# decoder.net
KiCad netlist of a schematic drawn in EAGLE
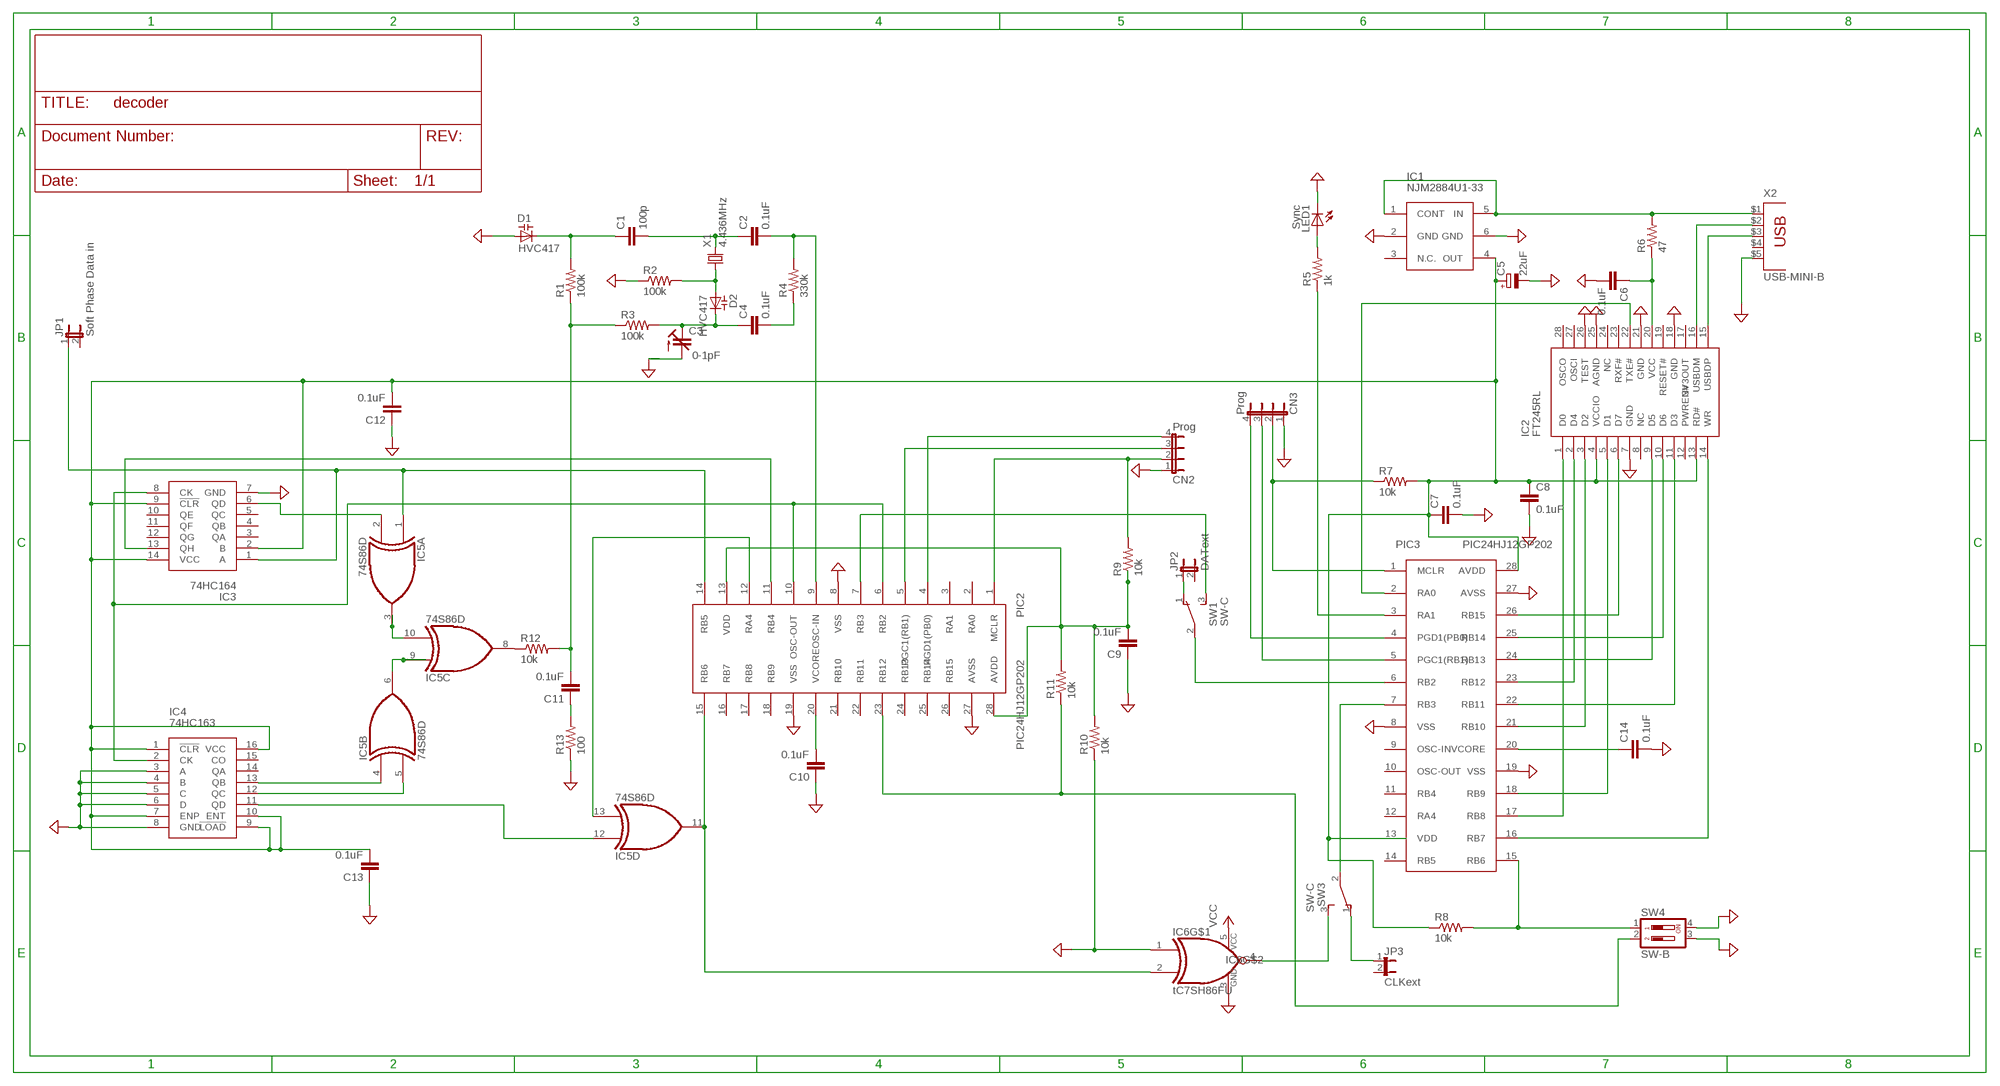
[diagram p0: schematic, sheet 1]

(export (version "E")
  (design (tool "Eeschema 10.0.6"))
  (components
    (comp (ref "C1")
      (value "100p")
      (footprint "eagle-import:C025-025X050")
      (libsource (lib "eagle-import") (part "C-EU025-025X050"))
    )
    (comp (ref "C2")
      (value "0.1uF")
      (footprint "eagle-import:C050-025X075")
      (libsource (lib "eagle-import") (part "resistor_C-EU050-025X075"))
    )
    (comp (ref "C3")
      (value "0-1pF")
      (footprint "eagle-import:CTRIMTZ03")
      (libsource (lib "eagle-import") (part "C-TRIMMTZ03"))
    )
    (comp (ref "C4")
      (value "0.1uF")
      (footprint "eagle-import:C050-025X075")
      (libsource (lib "eagle-import") (part "resistor_C-EU050-025X075"))
    )
    (comp (ref "C5")
      (value "22uF")
      (footprint "eagle-import:E3,5-8")
      (libsource (lib "eagle-import") (part "CPOL-EUE3.5-8"))
    )
    (comp (ref "C6")
      (value "0.1uF")
      (footprint "eagle-import:C050-025X075")
      (libsource (lib "eagle-import") (part "resistor_C-EU050-025X075"))
    )
    (comp (ref "C7")
      (value "0.1uF")
      (footprint "eagle-import:C050-025X075")
      (libsource (lib "eagle-import") (part "resistor_C-EU050-025X075"))
    )
    (comp (ref "C8")
      (value "0.1uF")
      (footprint "eagle-import:C050-025X075")
      (libsource (lib "eagle-import") (part "resistor_C-EU050-025X075"))
    )
    (comp (ref "C9")
      (value "0.1uF")
      (footprint "eagle-import:C050-025X075")
      (libsource (lib "eagle-import") (part "resistor_C-EU050-025X075"))
    )
    (comp (ref "C10")
      (value "0.1uF")
      (footprint "eagle-import:C050-025X075")
      (libsource (lib "eagle-import") (part "resistor_C-EU050-025X075"))
    )
    (comp (ref "C11")
      (value "0.1uF")
      (footprint "eagle-import:C050-025X075")
      (libsource (lib "eagle-import") (part "resistor_C-EU050-025X075"))
    )
    (comp (ref "C12")
      (value "0.1uF")
      (footprint "eagle-import:C050-025X075")
      (libsource (lib "eagle-import") (part "resistor_C-EU050-025X075"))
    )
    (comp (ref "C13")
      (value "0.1uF")
      (footprint "eagle-import:C050-025X075")
      (libsource (lib "eagle-import") (part "resistor_C-EU050-025X075"))
    )
    (comp (ref "C14")
      (value "0.1uF")
      (footprint "eagle-import:C050-025X075")
      (libsource (lib "eagle-import") (part "resistor_C-EU050-025X075"))
    )
    (comp (ref "CN2")
      (value "Prog")
      (footprint "eagle-import:JP4")
      (libsource (lib "eagle-import") (part "JP4E"))
    )
    (comp (ref "CN3")
      (value "Prog")
      (footprint "eagle-import:JP4")
      (libsource (lib "eagle-import") (part "JP4E"))
    )
    (comp (ref "D1")
      (value "HVC417")
      (footprint "eagle-import:SOT54H")
      (libsource (lib "eagle-import") (part "BB112"))
    )
    (comp (ref "D2")
      (value "HVC417")
      (footprint "eagle-import:SOT54H")
      (libsource (lib "eagle-import") (part "BB112"))
    )
    (comp (ref "IC1")
      (value "NJM2884U1-33")
      (footprint "eagle-import:NJM2884U1-33")
      (libsource (lib "eagle-import") (part "NJM2884U1-33"))
    )
    (comp (ref "IC2")
      (value "FT245RL")
      (footprint "eagle-import:FT245RL")
      (libsource (lib "eagle-import") (part "FT245RL"))
    )
    (comp (ref "IC3")
      (value "74HC164")
      (footprint "eagle-import:74HC164")
      (libsource (lib "eagle-import") (part "74HC164"))
    )
    (comp (ref "IC4")
      (value "74HC163")
      (footprint "eagle-import:74HC163")
      (libsource (lib "eagle-import") (part "74HC163"))
    )
    (comp (ref "IC5")
      (value "74S86D")
      (footprint "eagle-import:SO14")
      (libsource (lib "eagle-import") (part "7486DS"))
    )
    (comp (ref "IC6")
      (value "tC7SH86FU")
      (footprint "eagle-import:TC7SH86FU")
      (libsource (lib "eagle-import") (part "TC7SH86FU"))
    )
    (comp (ref "JP1")
      (value "Soft Phase Data in")
      (footprint "eagle-import:JP1")
      (libsource (lib "eagle-import") (part "JP1E"))
    )
    (comp (ref "JP2")
      (value "DAText")
      (footprint "eagle-import:JP1")
      (libsource (lib "eagle-import") (part "JP1E"))
    )
    (comp (ref "JP3")
      (value "CLKext")
      (footprint "eagle-import:JP1")
      (libsource (lib "eagle-import") (part "JP1E"))
    )
    (comp (ref "LED1")
      (value "Sync")
      (footprint "eagle-import:LED5MM")
      (libsource (lib "eagle-import") (part "LED5MM"))
    )
    (comp (ref "PIC2")
      (value "PIC24HJ12GP202")
      (footprint "eagle-import:PIC24HJ12GP202")
      (libsource (lib "eagle-import") (part "PIC24HJ12GP202"))
    )
    (comp (ref "PIC3")
      (value "PIC24HJ12GP202")
      (footprint "eagle-import:PIC24HJ12GP202")
      (libsource (lib "eagle-import") (part "PIC24HJ12GP202"))
    )
    (comp (ref "R1")
      (value "100k")
      (footprint "eagle-import:0207_7")
      (libsource (lib "eagle-import") (part "R-US_0207/7"))
    )
    (comp (ref "R2")
      (value "100k")
      (footprint "eagle-import:0207_7")
      (libsource (lib "eagle-import") (part "R-US_0207/7"))
    )
    (comp (ref "R3")
      (value "100k")
      (footprint "eagle-import:0207_7")
      (libsource (lib "eagle-import") (part "R-US_0207/7"))
    )
    (comp (ref "R4")
      (value "330k")
      (footprint "eagle-import:0207_7")
      (libsource (lib "eagle-import") (part "R-US_0207/7"))
    )
    (comp (ref "R5")
      (value "1k")
      (footprint "eagle-import:0207_7")
      (libsource (lib "eagle-import") (part "R-US_0207/7"))
    )
    (comp (ref "R6")
      (value "47")
      (footprint "eagle-import:0207_7")
      (libsource (lib "eagle-import") (part "R-US_0207/7"))
    )
    (comp (ref "R7")
      (value "10k")
      (footprint "eagle-import:0207_7")
      (libsource (lib "eagle-import") (part "R-US_0207/7"))
    )
    (comp (ref "R8")
      (value "10k")
      (footprint "eagle-import:0207_7")
      (libsource (lib "eagle-import") (part "R-US_0207/7"))
    )
    (comp (ref "R9")
      (value "10k")
      (footprint "eagle-import:0207_7")
      (libsource (lib "eagle-import") (part "R-US_0207/7"))
    )
    (comp (ref "R10")
      (value "10k")
      (footprint "eagle-import:0207_7")
      (libsource (lib "eagle-import") (part "R-US_0207/7"))
    )
    (comp (ref "R11")
      (value "10k")
      (footprint "eagle-import:0207_7")
      (libsource (lib "eagle-import") (part "R-US_0207/7"))
    )
    (comp (ref "R12")
      (value "10k")
      (footprint "eagle-import:0207_7")
      (libsource (lib "eagle-import") (part "R-US_0207/7"))
    )
    (comp (ref "R13")
      (value "100")
      (footprint "eagle-import:0207_7")
      (libsource (lib "eagle-import") (part "R-US_0207/7"))
    )
    (comp (ref "SW1")
      (value "SW-C")
      (footprint "eagle-import:TL3XPO")
      (libsource (lib "eagle-import") (part "TL36PO"))
    )
    (comp (ref "SW3")
      (value "SW-C")
      (footprint "eagle-import:TL3XPO")
      (libsource (lib "eagle-import") (part "TL36PO"))
    )
    (comp (ref "SW4")
      (value "SW-B")
      (footprint "eagle-import:DIP02YL")
      (libsource (lib "eagle-import") (part "DIP02YL"))
    )
    (comp (ref "X1")
      (value "4.436MHz")
      (footprint "eagle-import:HC49_S")
      (libsource (lib "eagle-import") (part "CRYSTALHC49S"))
    )
    (comp (ref "X2")
      (value "USB-MINI-B")
      (footprint "eagle-import:USB-MINI-B")
      (libsource (lib "eagle-import") (part "USB-MINI-B"))
    )
  )
  (nets
    (net (code "1") (name "/VDD") (class "Default")
      (node (ref "PIC3") (pin "13") (pinfunction "VDD_13") (pintype "power_in"))
    )
    (net (code "2") (name "GND") (class "Default")
      (node (ref "C10") (pin "1") (pinfunction "1_1") (pintype "passive"))
      (node (ref "C12") (pin "1") (pinfunction "1_1") (pintype "passive"))
      (node (ref "C13") (pin "1") (pinfunction "1_1") (pintype "passive"))
      (node (ref "C14") (pin "2") (pinfunction "2_2") (pintype "passive"))
      (node (ref "C3") (pin "2") (pinfunction "A_2") (pintype "passive"))
      (node (ref "C5") (pin "-") (pinfunction "-_-") (pintype "passive"))
      (node (ref "C6") (pin "2") (pinfunction "2_2") (pintype "passive"))
      (node (ref "C7") (pin "2") (pinfunction "2_2") (pintype "passive"))
      (node (ref "C8") (pin "2") (pinfunction "2_2") (pintype "passive"))
      (node (ref "C9") (pin "1") (pinfunction "1_1") (pintype "passive"))
      (node (ref "CN2") (pin "1") (pinfunction "1_1") (pintype "passive"))
      (node (ref "CN3") (pin "1") (pinfunction "1_1") (pintype "passive"))
      (node (ref "D1") (pin "A") (pinfunction "A_A") (pintype "passive"))
      (node (ref "IC1") (pin "2") (pinfunction "GND_2") (pintype "power_in"))
      (node (ref "IC1") (pin "6") (pinfunction "GND_6") (pintype "power_in"))
      (node (ref "IC2") (pin "18") (pinfunction "GND_18") (pintype "power_in"))
      (node (ref "IC2") (pin "21") (pinfunction "GND_21") (pintype "power_in"))
      (node (ref "IC2") (pin "25") (pinfunction "AGND_25") (pintype "power_in"))
      (node (ref "IC2") (pin "26") (pinfunction "TEST_26") (pintype "input"))
      (node (ref "IC2") (pin "7") (pinfunction "GND_7") (pintype "power_in"))
      (node (ref "IC3") (pin "7") (pinfunction "GND_7") (pintype "power_in"))
      (node (ref "IC4") (pin "3") (pinfunction "A_3") (pintype "input"))
      (node (ref "IC4") (pin "4") (pinfunction "B_4") (pintype "input"))
      (node (ref "IC4") (pin "5") (pinfunction "C_5") (pintype "input"))
      (node (ref "IC4") (pin "6") (pinfunction "D_6") (pintype "input"))
      (node (ref "IC4") (pin "8") (pinfunction "GND_8") (pintype "power_in"))
      (node (ref "IC6") (pin "1") (pinfunction "I0_1") (pintype "input"))
      (node (ref "IC6") (pin "3") (pinfunction "GND_3") (pintype "power_in"))
      (node (ref "LED1") (pin "K") (pinfunction "C_K") (pintype "passive"))
      (node (ref "PIC2") (pin "19") (pinfunction "VSS_19") (pintype "power_in"))
      (node (ref "PIC2") (pin "27") (pinfunction "AVSS_27") (pintype "power_in"))
      (node (ref "PIC2") (pin "8") (pinfunction "VSS_8") (pintype "power_in"))
      (node (ref "PIC3") (pin "19") (pinfunction "VSS_19") (pintype "power_in"))
      (node (ref "PIC3") (pin "27") (pinfunction "AVSS_27") (pintype "power_in"))
      (node (ref "PIC3") (pin "8") (pinfunction "VSS_8") (pintype "power_in"))
      (node (ref "R10") (pin "1") (pinfunction "1_1") (pintype "passive"))
      (node (ref "R13") (pin "1") (pinfunction "1_1") (pintype "passive"))
      (node (ref "R2") (pin "1") (pinfunction "1_1") (pintype "passive"))
      (node (ref "SW4") (pin "3") (pinfunction "3_3") (pintype "passive"))
      (node (ref "SW4") (pin "4") (pinfunction "4_4") (pintype "passive"))
      (node (ref "X2") (pin "$5") (pinfunction "5_$5") (pintype "bidirectional"))
    )
    (net (code "3") (name "Net-(C1-Pad1)") (class "Default")
      (node (ref "C1") (pin "1") (pinfunction "1_1") (pintype "passive"))
      (node (ref "D1") (pin "C") (pinfunction "C_C") (pintype "passive"))
      (node (ref "R1") (pin "2") (pinfunction "2_2") (pintype "passive"))
    )
    (net (code "4") (name "Net-(C1-Pad2)") (class "Default")
      (node (ref "C1") (pin "2") (pinfunction "2_2") (pintype "passive"))
      (node (ref "C2") (pin "1") (pinfunction "1_1") (pintype "passive"))
      (node (ref "X1") (pin "2") (pinfunction "2_2") (pintype "passive"))
    )
    (net (code "5") (name "Net-(C3-E)") (class "Default")
      (node (ref "C3") (pin "1") (pinfunction "E_1") (pintype "passive"))
      (node (ref "C4") (pin "1") (pinfunction "1_1") (pintype "passive"))
      (node (ref "D2") (pin "C") (pinfunction "C_C") (pintype "passive"))
      (node (ref "R3") (pin "2") (pinfunction "2_2") (pintype "passive"))
    )
    (net (code "6") (name "Net-(C4-Pad2)") (class "Default")
      (node (ref "C4") (pin "2") (pinfunction "2_2") (pintype "passive"))
      (node (ref "R4") (pin "1") (pinfunction "1_1") (pintype "passive"))
    )
    (net (code "7") (name "Net-(C11-Pad1)") (class "Default")
      (node (ref "C11") (pin "1") (pinfunction "1_1") (pintype "passive"))
      (node (ref "R13") (pin "2") (pinfunction "2_2") (pintype "passive"))
    )
    (net (code "8") (name "Net-(C11-Pad2)") (class "Default")
      (node (ref "C11") (pin "2") (pinfunction "2_2") (pintype "passive"))
      (node (ref "R1") (pin "1") (pinfunction "1_1") (pintype "passive"))
      (node (ref "R12") (pin "2") (pinfunction "2_2") (pintype "passive"))
      (node (ref "R3") (pin "1") (pinfunction "1_1") (pintype "passive"))
    )
    (net (code "9") (name "Net-(D2-PadA)") (class "Default")
      (node (ref "D2") (pin "A") (pinfunction "A_A") (pintype "passive"))
      (node (ref "R2") (pin "2") (pinfunction "2_2") (pintype "passive"))
      (node (ref "X1") (pin "1") (pinfunction "1_1") (pintype "passive"))
    )
    (net (code "10") (name "Net-(IC1-CONT)") (class "Default")
      (node (ref "IC1") (pin "1") (pinfunction "CONT_1") (pintype "bidirectional"))
      (node (ref "IC1") (pin "5") (pinfunction "IN_5") (pintype "input"))
      (node (ref "R6") (pin "2") (pinfunction "2_2") (pintype "passive"))
      (node (ref "X2") (pin "$1") (pinfunction "1_$1") (pintype "bidirectional"))
    )
    (net (code "11") (name "Net-(IC1-OUT)") (class "Default")
      (node (ref "C12") (pin "2") (pinfunction "2_2") (pintype "passive"))
      (node (ref "C13") (pin "2") (pinfunction "2_2") (pintype "passive"))
      (node (ref "C5") (pin "+") (pinfunction "+_+") (pintype "passive"))
      (node (ref "C7") (pin "1") (pinfunction "1_1") (pintype "passive"))
      (node (ref "C8") (pin "1") (pinfunction "1_1") (pintype "passive"))
      (node (ref "IC1") (pin "4") (pinfunction "OUT_4") (pintype "output"))
      (node (ref "IC2") (pin "13") (pinfunction "RD#_13") (pintype "input"))
      (node (ref "IC2") (pin "4") (pinfunction "VCCIO_4") (pintype "power_in"))
      (node (ref "IC3") (pin "14") (pinfunction "VCC_14") (pintype "power_in"))
      (node (ref "IC3") (pin "2") (pinfunction "B_2") (pintype "input"))
      (node (ref "IC3") (pin "9") (pinfunction "~{CLR}_9") (pintype "input"))
      (node (ref "IC4") (pin "1") (pinfunction "~{CLR}_1") (pintype "input"))
      (node (ref "IC4") (pin "10") (pinfunction "ENT_10") (pintype "input"))
      (node (ref "IC4") (pin "16") (pinfunction "VCC_16") (pintype "power_in"))
      (node (ref "IC4") (pin "7") (pinfunction "ENP_7") (pintype "input"))
      (node (ref "IC4") (pin "9") (pinfunction "~{LOAD}_9") (pintype "input"))
      (node (ref "PIC3") (pin "28") (pinfunction "AVDD_28") (pintype "power_in"))
      (node (ref "R7") (pin "2") (pinfunction "2_2") (pintype "passive"))
      (node (ref "R8") (pin "1") (pinfunction "1_1") (pintype "passive"))
    )
    (net (code "12") (name "Net-(IC2-D0)") (class "Default")
      (node (ref "IC2") (pin "1") (pinfunction "D0_1") (pintype "bidirectional"))
      (node (ref "PIC3") (pin "17") (pinfunction "RB8_17") (pintype "bidirectional"))
    )
    (net (code "13") (name "Net-(IC2-D1)") (class "Default")
      (node (ref "IC2") (pin "5") (pinfunction "D1_5") (pintype "bidirectional"))
      (node (ref "PIC3") (pin "18") (pinfunction "RB9_18") (pintype "bidirectional"))
    )
    (net (code "14") (name "Net-(IC2-D2)") (class "Default")
      (node (ref "IC2") (pin "3") (pinfunction "D2_3") (pintype "bidirectional"))
      (node (ref "PIC3") (pin "21") (pinfunction "RB10_21") (pintype "bidirectional"))
    )
    (net (code "15") (name "Net-(IC2-D3)") (class "Default")
      (node (ref "IC2") (pin "11") (pinfunction "D3_11") (pintype "bidirectional"))
      (node (ref "PIC3") (pin "22") (pinfunction "RB11_22") (pintype "bidirectional"))
    )
    (net (code "16") (name "Net-(IC2-D4)") (class "Default")
      (node (ref "IC2") (pin "2") (pinfunction "D4_2") (pintype "bidirectional"))
      (node (ref "PIC3") (pin "23") (pinfunction "RB12_23") (pintype "input"))
    )
    (net (code "17") (name "Net-(IC2-D5)") (class "Default")
      (node (ref "IC2") (pin "9") (pinfunction "D5_9") (pintype "bidirectional"))
      (node (ref "PIC3") (pin "24") (pinfunction "RB13_24") (pintype "input"))
    )
    (net (code "18") (name "Net-(IC2-D6)") (class "Default")
      (node (ref "IC2") (pin "10") (pinfunction "D6_10") (pintype "bidirectional"))
      (node (ref "PIC3") (pin "25") (pinfunction "RB14_25") (pintype "input"))
    )
    (net (code "19") (name "Net-(IC2-D7)") (class "Default")
      (node (ref "IC2") (pin "6") (pinfunction "D7_6") (pintype "bidirectional"))
      (node (ref "PIC3") (pin "26") (pinfunction "RB15_26") (pintype "input"))
    )
    (net (code "20") (name "Net-(IC2-TXE#)") (class "Default")
      (node (ref "IC2") (pin "22") (pinfunction "TXE#_22") (pintype "output"))
      (node (ref "PIC3") (pin "2") (pinfunction "RA0_2") (pintype "bidirectional"))
    )
    (net (code "21") (name "Net-(IC2-USBDM)") (class "Default")
      (node (ref "IC2") (pin "16") (pinfunction "USBDM_16") (pintype "bidirectional"))
      (node (ref "X2") (pin "$2") (pinfunction "2_$2") (pintype "bidirectional"))
    )
    (net (code "22") (name "Net-(IC2-USBDP)") (class "Default")
      (node (ref "IC2") (pin "15") (pinfunction "USBDP_15") (pintype "bidirectional"))
      (node (ref "X2") (pin "$3") (pinfunction "3_$3") (pintype "bidirectional"))
    )
    (net (code "23") (name "Net-(IC2-VCC)") (class "Default")
      (node (ref "C6") (pin "1") (pinfunction "1_1") (pintype "passive"))
      (node (ref "IC2") (pin "20") (pinfunction "VCC_20") (pintype "power_in"))
      (node (ref "R6") (pin "1") (pinfunction "1_1") (pintype "passive"))
    )
    (net (code "24") (name "Net-(IC2-WR)") (class "Default")
      (node (ref "IC2") (pin "14") (pinfunction "WR_14") (pintype "input"))
      (node (ref "PIC3") (pin "16") (pinfunction "RB7_16") (pintype "bidirectional"))
    )
    (net (code "25") (name "Net-(IC3-A)") (class "Default")
      (node (ref "IC3") (pin "1") (pinfunction "A_1") (pintype "input"))
      (node (ref "IC5") (pin "1") (pinfunction "I0_1") (pintype "input"))
      (node (ref "JP1") (pin "1") (pinfunction "1_1") (pintype "passive"))
      (node (ref "PIC2") (pin "14") (pinfunction "RB5_14") (pintype "bidirectional"))
    )
    (net (code "26") (name "Net-(IC3-CK)") (class "Default")
      (node (ref "IC3") (pin "8") (pinfunction "CK_8") (pintype "input"))
      (node (ref "IC4") (pin "2") (pinfunction "CK_2") (pintype "input"))
      (node (ref "PIC2") (pin "10") (pinfunction "OSC-OUT_10") (pintype "output"))
      (node (ref "PIC2") (pin "6") (pinfunction "RB2_6") (pintype "bidirectional"))
    )
    (net (code "27") (name "Net-(IC3-QD)") (class "Default")
      (node (ref "IC3") (pin "6") (pinfunction "QD_6") (pintype "output"))
      (node (ref "IC5") (pin "2") (pinfunction "I1_2") (pintype "input"))
    )
    (net (code "28") (name "Net-(IC3-QH)") (class "Default")
      (node (ref "IC3") (pin "13") (pinfunction "QH_13") (pintype "output"))
      (node (ref "PIC2") (pin "11") (pinfunction "RB4_11") (pintype "bidirectional"))
    )
    (net (code "29") (name "Net-(IC4-QB)") (class "Default")
      (node (ref "IC4") (pin "13") (pinfunction "QB_13") (pintype "output"))
      (node (ref "IC5") (pin "4") (pinfunction "I0_4") (pintype "input"))
    )
    (net (code "30") (name "Net-(IC4-QC)") (class "Default")
      (node (ref "IC4") (pin "12") (pinfunction "QC_12") (pintype "output"))
      (node (ref "IC5") (pin "5") (pinfunction "I1_5") (pintype "input"))
    )
    (net (code "31") (name "Net-(IC4-QD)") (class "Default")
      (node (ref "IC4") (pin "11") (pinfunction "QD_11") (pintype "output"))
      (node (ref "IC5") (pin "12") (pinfunction "I0_12") (pintype "input"))
    )
    (net (code "32") (name "Net-(IC5A-O)") (class "Default")
      (node (ref "IC5") (pin "10") (pinfunction "I1_10") (pintype "input"))
      (node (ref "IC5") (pin "3") (pinfunction "O_3") (pintype "output"))
    )
    (net (code "33") (name "Net-(IC5B-O)") (class "Default")
      (node (ref "IC5") (pin "6") (pinfunction "O_6") (pintype "output"))
      (node (ref "IC5") (pin "9") (pinfunction "I0_9") (pintype "input"))
    )
    (net (code "34") (name "Net-(IC5C-O)") (class "Default")
      (node (ref "IC5") (pin "8") (pinfunction "O_8") (pintype "output"))
      (node (ref "R12") (pin "1") (pinfunction "1_1") (pintype "passive"))
    )
    (net (code "35") (name "Net-(IC5D-I1)") (class "Default")
      (node (ref "IC5") (pin "13") (pinfunction "I1_13") (pintype "input"))
      (node (ref "PIC2") (pin "12") (pinfunction "RA4_12") (pintype "input"))
    )
    (net (code "36") (name "Net-(IC5D-O)") (class "Default")
      (node (ref "IC5") (pin "11") (pinfunction "O_11") (pintype "output"))
      (node (ref "IC6") (pin "2") (pinfunction "I1_2") (pintype "input"))
      (node (ref "PIC2") (pin "15") (pinfunction "RB6_15") (pintype "bidirectional"))
    )
    (net (code "37") (name "Net-(IC6A-O)") (class "Default")
      (node (ref "IC6") (pin "4") (pinfunction "O_4") (pintype "open_collector"))
      (node (ref "SW3") (pin "3") (pinfunction "S_3") (pintype "passive"))
    )
    (net (code "38") (name "Net-(LED1-PadA)") (class "Default")
      (node (ref "LED1") (pin "A") (pinfunction "A_A") (pintype "passive"))
      (node (ref "R5") (pin "2") (pinfunction "2_2") (pintype "passive"))
    )
    (net (code "39") (name "Net-(PIC2-AVDD)") (class "Default")
      (node (ref "C9") (pin "2") (pinfunction "2_2") (pintype "passive"))
      (node (ref "PIC2") (pin "13") (pinfunction "VDD_13") (pintype "power_in"))
      (node (ref "PIC2") (pin "28") (pinfunction "AVDD_28") (pintype "power_in"))
      (node (ref "R10") (pin "2") (pinfunction "2_2") (pintype "passive"))
      (node (ref "R11") (pin "2") (pinfunction "2_2") (pintype "passive"))
      (node (ref "R9") (pin "1") (pinfunction "1_1") (pintype "passive"))
    )
    (net (code "40") (name "Net-(PIC2-MCLR)") (class "Default")
      (node (ref "CN2") (pin "2") (pinfunction "2_2") (pintype "passive"))
      (node (ref "PIC2") (pin "1") (pinfunction "MCLR_1") (pintype "input"))
      (node (ref "R9") (pin "2") (pinfunction "2_2") (pintype "passive"))
    )
    (net (code "41") (name "Net-(PIC2-OSC-IN)") (class "Default")
      (node (ref "C2") (pin "2") (pinfunction "2_2") (pintype "passive"))
      (node (ref "PIC2") (pin "9") (pinfunction "OSC-IN_9") (pintype "bidirectional"))
      (node (ref "R4") (pin "2") (pinfunction "2_2") (pintype "passive"))
    )
    (net (code "42") (name "Net-(PIC2-PGC1(RB1))") (class "Default")
      (node (ref "CN2") (pin "3") (pinfunction "3_3") (pintype "passive"))
      (node (ref "PIC2") (pin "5") (pinfunction "PGC1(RB1)_5") (pintype "input"))
    )
    (net (code "43") (name "Net-(PIC2-PGD1(PB0))") (class "Default")
      (node (ref "CN2") (pin "4") (pinfunction "4_4") (pintype "passive"))
      (node (ref "PIC2") (pin "4") (pinfunction "PGD1(PB0)_4") (pintype "bidirectional"))
    )
    (net (code "44") (name "Net-(PIC2-RB3)") (class "Default")
      (node (ref "PIC2") (pin "7") (pinfunction "RB3_7") (pintype "bidirectional"))
      (node (ref "SW1") (pin "3") (pinfunction "S_3") (pintype "passive"))
    )
    (net (code "45") (name "Net-(PIC2-RB12)") (class "Default")
      (node (ref "PIC2") (pin "23") (pinfunction "RB12_23") (pintype "input"))
      (node (ref "R11") (pin "1") (pinfunction "1_1") (pintype "passive"))
      (node (ref "SW4") (pin "2") (pinfunction "2_2") (pintype "passive"))
    )
    (net (code "46") (name "Net-(PIC2-VCORE)") (class "Default")
      (node (ref "C10") (pin "2") (pinfunction "2_2") (pintype "passive"))
      (node (ref "PIC2") (pin "20") (pinfunction "VCORE_20") (pintype "power_in"))
    )
    (net (code "47") (name "Net-(PIC3-MCLR)") (class "Default")
      (node (ref "CN3") (pin "2") (pinfunction "2_2") (pintype "passive"))
      (node (ref "PIC3") (pin "1") (pinfunction "MCLR_1") (pintype "input"))
      (node (ref "R7") (pin "1") (pinfunction "1_1") (pintype "passive"))
    )
    (net (code "48") (name "Net-(PIC3-PGC1(RB1))") (class "Default")
      (node (ref "CN3") (pin "3") (pinfunction "3_3") (pintype "passive"))
      (node (ref "PIC3") (pin "5") (pinfunction "PGC1(RB1)_5") (pintype "input"))
    )
    (net (code "49") (name "Net-(PIC3-PGD1(PB0))") (class "Default")
      (node (ref "CN3") (pin "4") (pinfunction "4_4") (pintype "passive"))
      (node (ref "PIC3") (pin "4") (pinfunction "PGD1(PB0)_4") (pintype "bidirectional"))
    )
    (net (code "50") (name "Net-(PIC3-RA1)") (class "Default")
      (node (ref "PIC3") (pin "3") (pinfunction "RA1_3") (pintype "input"))
      (node (ref "R5") (pin "1") (pinfunction "1_1") (pintype "passive"))
    )
    (net (code "51") (name "Net-(PIC3-RB2)") (class "Default")
      (node (ref "PIC3") (pin "6") (pinfunction "RB2_6") (pintype "bidirectional"))
      (node (ref "SW1") (pin "2") (pinfunction "P_2") (pintype "passive"))
    )
    (net (code "52") (name "Net-(PIC3-RB3)") (class "Default")
      (node (ref "PIC3") (pin "7") (pinfunction "RB3_7") (pintype "bidirectional"))
      (node (ref "SW3") (pin "2") (pinfunction "P_2") (pintype "passive"))
    )
    (net (code "53") (name "Net-(PIC3-RB6)") (class "Default")
      (node (ref "PIC3") (pin "15") (pinfunction "RB6_15") (pintype "bidirectional"))
      (node (ref "R8") (pin "2") (pinfunction "2_2") (pintype "passive"))
      (node (ref "SW4") (pin "1") (pinfunction "1_1") (pintype "passive"))
    )
    (net (code "54") (name "Net-(PIC3-VCORE)") (class "Default")
      (node (ref "C14") (pin "1") (pinfunction "1_1") (pintype "passive"))
      (node (ref "PIC3") (pin "20") (pinfunction "VCORE_20") (pintype "power_in"))
    )
    (net (code "55") (name "Net-(SW1-O)") (class "Default")
      (node (ref "JP2") (pin "1") (pinfunction "1_1") (pintype "passive"))
      (node (ref "SW1") (pin "1") (pinfunction "O_1") (pintype "passive"))
    )
    (net (code "56") (name "Net-(SW3-O)") (class "Default")
      (node (ref "JP3") (pin "1") (pinfunction "1_1") (pintype "passive"))
      (node (ref "SW3") (pin "1") (pinfunction "O_1") (pintype "passive"))
    )
    (net (code "57") (name "VCC") (class "Default")
      (node (ref "IC6") (pin "5") (pinfunction "VCC_5") (pintype "power_in"))
    )
    (net (code "58") (name "unconnected-(IC1-N.C.-Pad3)") (class "Default")
      (node (ref "IC1") (pin "3") (pinfunction "N.C._3") (pintype "no_connect"))
    )
    (net (code "59") (name "unconnected-(IC2-3V3OUT-Pad17)") (class "Default")
      (node (ref "IC2") (pin "17") (pinfunction "3V3OUT_17") (pintype "output"))
    )
    (net (code "60") (name "unconnected-(IC2-NC-Pad8)") (class "Default")
      (node (ref "IC2") (pin "8") (pinfunction "NC_8") (pintype "no_connect"))
    )
    (net (code "61") (name "unconnected-(IC2-NC-Pad24)") (class "Default")
      (node (ref "IC2") (pin "24") (pinfunction "NC_24") (pintype "no_connect"))
    )
    (net (code "62") (name "unconnected-(IC2-OSCI-Pad27)") (class "Default")
      (node (ref "IC2") (pin "27") (pinfunction "OSCI_27") (pintype "input"))
    )
    (net (code "63") (name "unconnected-(IC2-OSCO-Pad28)") (class "Default")
      (node (ref "IC2") (pin "28") (pinfunction "OSCO_28") (pintype "output"))
    )
    (net (code "64") (name "unconnected-(IC2-PWREN#-Pad12)") (class "Default")
      (node (ref "IC2") (pin "12") (pinfunction "PWREN#_12") (pintype "output"))
    )
    (net (code "65") (name "unconnected-(IC2-RESET#-Pad19)") (class "Default")
      (node (ref "IC2") (pin "19") (pinfunction "RESET#_19") (pintype "input"))
    )
    (net (code "66") (name "unconnected-(IC2-RXF#-Pad23)") (class "Default")
      (node (ref "IC2") (pin "23") (pinfunction "RXF#_23") (pintype "output"))
    )
    (net (code "67") (name "unconnected-(IC3-QA-Pad3)") (class "Default")
      (node (ref "IC3") (pin "3") (pinfunction "QA_3") (pintype "output"))
    )
    (net (code "68") (name "unconnected-(IC3-QB-Pad4)") (class "Default")
      (node (ref "IC3") (pin "4") (pinfunction "QB_4") (pintype "output"))
    )
    (net (code "69") (name "unconnected-(IC3-QC-Pad5)") (class "Default")
      (node (ref "IC3") (pin "5") (pinfunction "QC_5") (pintype "output"))
    )
    (net (code "70") (name "unconnected-(IC3-QE-Pad10)") (class "Default")
      (node (ref "IC3") (pin "10") (pinfunction "QE_10") (pintype "output"))
    )
    (net (code "71") (name "unconnected-(IC3-QF-Pad11)") (class "Default")
      (node (ref "IC3") (pin "11") (pinfunction "QF_11") (pintype "output"))
    )
    (net (code "72") (name "unconnected-(IC3-QG-Pad12)") (class "Default")
      (node (ref "IC3") (pin "12") (pinfunction "QG_12") (pintype "output"))
    )
    (net (code "73") (name "unconnected-(IC4-CO-Pad15)") (class "Default")
      (node (ref "IC4") (pin "15") (pinfunction "CO_15") (pintype "bidirectional"))
    )
    (net (code "74") (name "unconnected-(IC4-QA-Pad14)") (class "Default")
      (node (ref "IC4") (pin "14") (pinfunction "QA_14") (pintype "output"))
    )
    (net (code "75") (name "unconnected-(JP1-Pad2)") (class "Default")
      (node (ref "JP1") (pin "2") (pinfunction "2_2") (pintype "passive"))
    )
    (net (code "76") (name "unconnected-(JP2-Pad2)") (class "Default")
      (node (ref "JP2") (pin "2") (pinfunction "2_2") (pintype "passive"))
    )
    (net (code "77") (name "unconnected-(JP3-Pad2)") (class "Default")
      (node (ref "JP3") (pin "2") (pinfunction "2_2") (pintype "passive"))
    )
    (net (code "78") (name "unconnected-(PIC2-RA0-Pad2)") (class "Default")
      (node (ref "PIC2") (pin "2") (pinfunction "RA0_2") (pintype "bidirectional"))
    )
    (net (code "79") (name "unconnected-(PIC2-RA1-Pad3)") (class "Default")
      (node (ref "PIC2") (pin "3") (pinfunction "RA1_3") (pintype "input"))
    )
    (net (code "80") (name "unconnected-(PIC2-RB7-Pad16)") (class "Default")
      (node (ref "PIC2") (pin "16") (pinfunction "RB7_16") (pintype "bidirectional"))
    )
    (net (code "81") (name "unconnected-(PIC2-RB8-Pad17)") (class "Default")
      (node (ref "PIC2") (pin "17") (pinfunction "RB8_17") (pintype "bidirectional"))
    )
    (net (code "82") (name "unconnected-(PIC2-RB9-Pad18)") (class "Default")
      (node (ref "PIC2") (pin "18") (pinfunction "RB9_18") (pintype "bidirectional"))
    )
    (net (code "83") (name "unconnected-(PIC2-RB10-Pad21)") (class "Default")
      (node (ref "PIC2") (pin "21") (pinfunction "RB10_21") (pintype "bidirectional"))
    )
    (net (code "84") (name "unconnected-(PIC2-RB11-Pad22)") (class "Default")
      (node (ref "PIC2") (pin "22") (pinfunction "RB11_22") (pintype "bidirectional"))
    )
    (net (code "85") (name "unconnected-(PIC2-RB13-Pad24)") (class "Default")
      (node (ref "PIC2") (pin "24") (pinfunction "RB13_24") (pintype "input"))
    )
    (net (code "86") (name "unconnected-(PIC2-RB14-Pad25)") (class "Default")
      (node (ref "PIC2") (pin "25") (pinfunction "RB14_25") (pintype "input"))
    )
    (net (code "87") (name "unconnected-(PIC2-RB15-Pad26)") (class "Default")
      (node (ref "PIC2") (pin "26") (pinfunction "RB15_26") (pintype "input"))
    )
    (net (code "88") (name "unconnected-(PIC3-OSC-IN-Pad9)") (class "Default")
      (node (ref "PIC3") (pin "9") (pinfunction "OSC-IN_9") (pintype "bidirectional"))
    )
    (net (code "89") (name "unconnected-(PIC3-OSC-OUT-Pad10)") (class "Default")
      (node (ref "PIC3") (pin "10") (pinfunction "OSC-OUT_10") (pintype "output"))
    )
    (net (code "90") (name "unconnected-(PIC3-RA4-Pad12)") (class "Default")
      (node (ref "PIC3") (pin "12") (pinfunction "RA4_12") (pintype "input"))
    )
    (net (code "91") (name "unconnected-(PIC3-RB4-Pad11)") (class "Default")
      (node (ref "PIC3") (pin "11") (pinfunction "RB4_11") (pintype "bidirectional"))
    )
    (net (code "92") (name "unconnected-(PIC3-RB5-Pad14)") (class "Default")
      (node (ref "PIC3") (pin "14") (pinfunction "RB5_14") (pintype "bidirectional"))
    )
    (net (code "93") (name "unconnected-(X2-4-Pad$4)") (class "Default")
      (node (ref "X2") (pin "$4") (pinfunction "4_$4") (pintype "bidirectional"))
    )
  )
)
